# pqm_v2_page2.net
KiCad netlist of a schematic drawn in Altium Designer
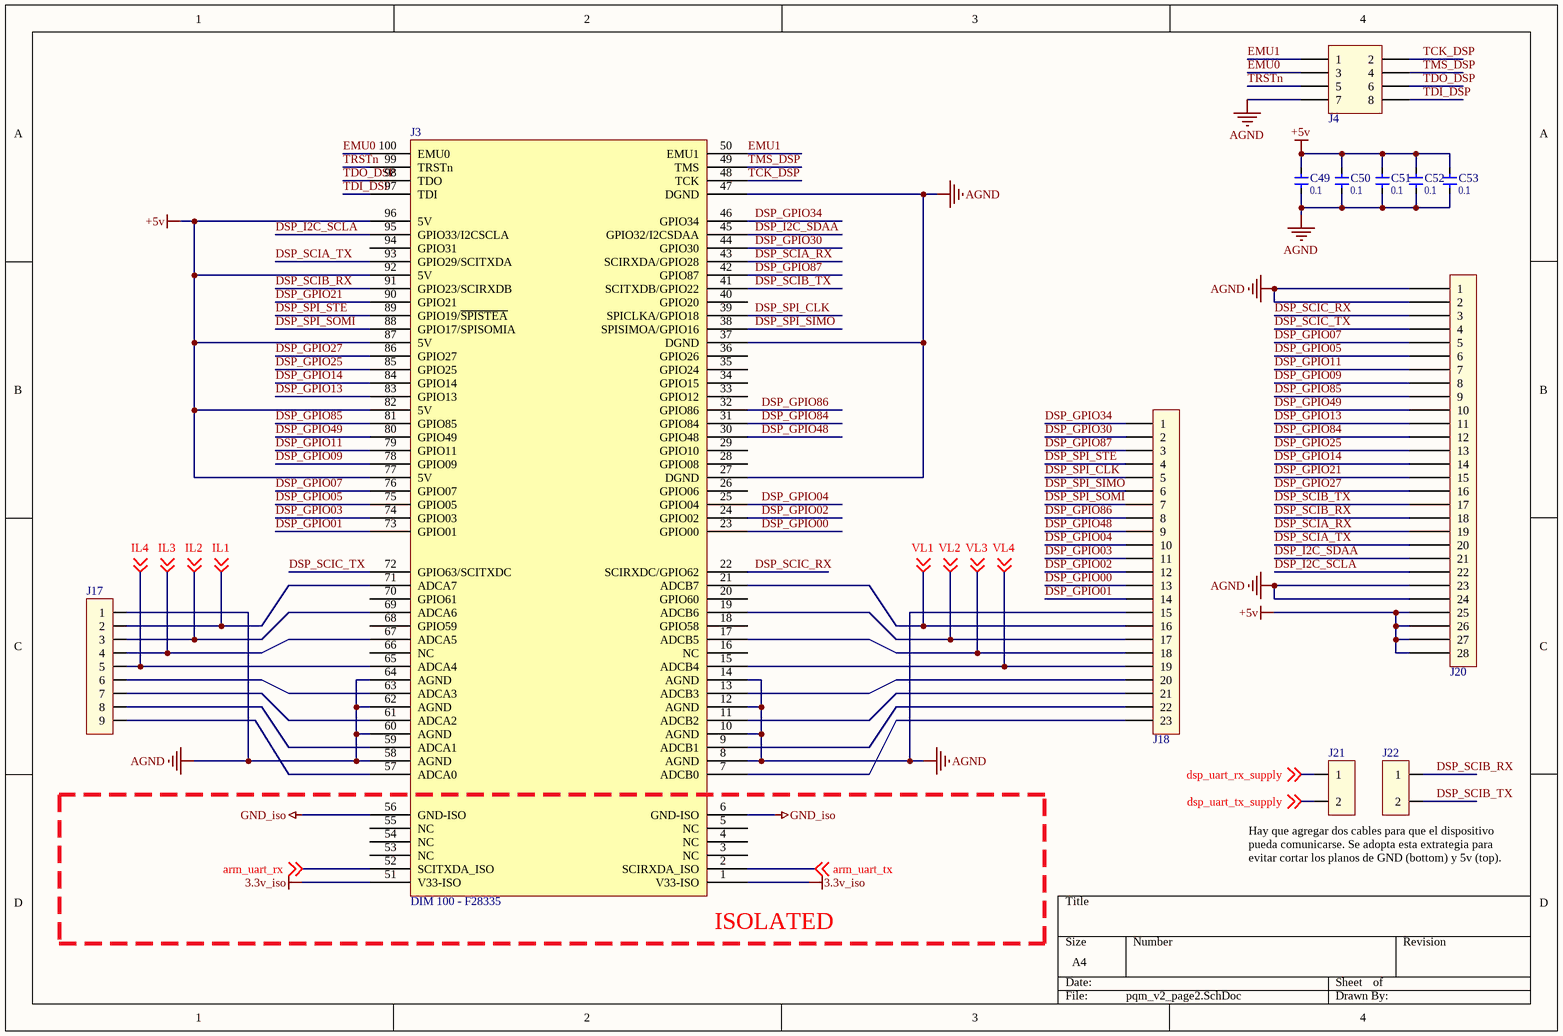
[diagram p0: pqm_v2_page2.SchDoc]

(export (version "E")
  (design (tool "Eeschema 10.0.6"))
  (components
    (comp (ref "C49")
      (value "0.1")
      (footprint "CAPC2013X110N")
      (description "CAP CER 0.1UF 25V 10% X7R 0805")
      (fields (field (name "MANUFACTURER") "Yageo") (field (name "TOLERANCE") "10%"))
      (libsource (lib "pqm_v2_lib_cap") (part "CAP_CC0805KRX7R8BB104_YAGEO"))
    )
    (comp (ref "C50")
      (value "0.1")
      (footprint "CAPC2013X110N")
      (description "CAP CER 0.1UF 25V 10% X7R 0805")
      (fields (field (name "MANUFACTURER") "Yageo") (field (name "TOLERANCE") "10%"))
      (libsource (lib "pqm_v2_lib_cap") (part "CAP_CC0805KRX7R8BB104_YAGEO"))
    )
    (comp (ref "C51")
      (value "0.1")
      (footprint "CAPC2013X110N")
      (description "CAP CER 0.1UF 25V 10% X7R 0805")
      (fields (field (name "MANUFACTURER") "Yageo") (field (name "TOLERANCE") "10%"))
      (libsource (lib "pqm_v2_lib_cap") (part "CAP_CC0805KRX7R8BB104_YAGEO"))
    )
    (comp (ref "C52")
      (value "0.1")
      (footprint "CAPC2013X110N")
      (description "CAP CER 0.1UF 25V 10% X7R 0805")
      (fields (field (name "MANUFACTURER") "Yageo") (field (name "TOLERANCE") "10%"))
      (libsource (lib "pqm_v2_lib_cap") (part "CAP_CC0805KRX7R8BB104_YAGEO"))
    )
    (comp (ref "C53")
      (value "0.1")
      (footprint "CAPC2013X110N")
      (description "CAP CER 0.1UF 25V 10% X7R 0805")
      (fields (field (name "MANUFACTURER") "Yageo") (field (name "TOLERANCE") "10%"))
      (libsource (lib "pqm_v2_lib_cap") (part "CAP_CC0805KRX7R8BB104_YAGEO"))
    )
    (comp (ref "J3")
      (value "DIM 100 - F28335")
      (footprint "DIMM1.27-2V100")
      (fields
        (field (name "DIGIKEY PART NUMBER") "A121375-ND")
        (field (name "MANUFACTURER PART NUMBER") "5390213-1")
        (field (name "MOUSER PART NUMBER") "571-5390213-1")
      )
      (libsource (lib "pqm_v2_lib_connectors") (part "CON_DIM_100"))
    )
    (comp (ref "J4")
      (value "CON_Header_2X4")
      (footprint "HDR2X4")
      (libsource (lib "pqm_v2_lib_connectors") (part "CON_Header_2X4"))
    )
    (comp (ref "J17")
      (value "COM_HeaderX9")
      (footprint "HDRX9")
      (libsource (lib "pqm_v2_lib_connectors") (part "COM_HeaderX9"))
    )
    (comp (ref "J18")
      (value "Header_DSP_1")
      (footprint "HEADER_DSP_1")
      (libsource (lib "pqm_v2_lib_connectors") (part "Header_DSP_1"))
    )
    (comp (ref "J20")
      (value "CON_HeaderX30")
      (footprint "HeaderX30")
      (libsource (lib "pqm_v2_lib_connectors") (part "CON_HeaderX30"))
    )
    (comp (ref "J21") (value "CON_RADX2b") (footprint "RAD2b") (libsource (lib "") (part "CON_RADX2b_1")))
    (comp (ref "J22")
      (value "CON_RADX2b")
      (footprint "RAD2b")
      (libsource (lib "pqm_v2_lib_connectors") (part "CON_RADX2b"))
    )
  )
  (nets
    (net (code "1") (name "+5v") (class "Default")
      (node (ref "C49") (pin "1") (pinfunction "T1_1") (pintype "passive"))
      (node (ref "C50") (pin "1") (pinfunction "T1_1") (pintype "passive"))
      (node (ref "C51") (pin "1") (pinfunction "T1_1") (pintype "passive"))
      (node (ref "C52") (pin "1") (pinfunction "T1_1") (pintype "passive"))
      (node (ref "C53") (pin "1") (pinfunction "T1_1") (pintype "passive"))
      (node (ref "J20") (pin "25") (pinfunction "25_25") (pintype "passive"))
      (node (ref "J20") (pin "26") (pinfunction "26_26") (pintype "passive"))
      (node (ref "J20") (pin "27") (pinfunction "27_27") (pintype "passive"))
      (node (ref "J20") (pin "28") (pinfunction "28_28") (pintype "passive"))
      (node (ref "J3") (pin "77") (pinfunction "5V_77") (pintype "passive"))
      (node (ref "J3") (pin "82") (pinfunction "5V_82") (pintype "passive"))
      (node (ref "J3") (pin "87") (pinfunction "5V_87") (pintype "passive"))
      (node (ref "J3") (pin "92") (pinfunction "5V_92") (pintype "passive"))
      (node (ref "J3") (pin "96") (pinfunction "5V_96") (pintype "passive"))
    )
    (net (code "2") (name "/DSP_GPIO00") (class "Default")
      (node (ref "J18") (pin "13") (pinfunction "13_13") (pintype "passive"))
      (node (ref "J3") (pin "23") (pinfunction "GPIO00_23") (pintype "passive"))
    )
    (net (code "3") (name "/DSP_GPIO01") (class "Default")
      (node (ref "J18") (pin "14") (pinfunction "14_14") (pintype "passive"))
      (node (ref "J3") (pin "73") (pinfunction "GPIO01_73") (pintype "passive"))
    )
    (net (code "4") (name "/DSP_GPIO02") (class "Default")
      (node (ref "J18") (pin "12") (pinfunction "12_12") (pintype "passive"))
      (node (ref "J3") (pin "24") (pinfunction "GPIO02_24") (pintype "passive"))
    )
    (net (code "5") (name "/DSP_GPIO03") (class "Default")
      (node (ref "J18") (pin "11") (pinfunction "11_11") (pintype "passive"))
      (node (ref "J3") (pin "74") (pinfunction "GPIO03_74") (pintype "passive"))
    )
    (net (code "6") (name "/DSP_GPIO04") (class "Default")
      (node (ref "J18") (pin "10") (pinfunction "10_10") (pintype "passive"))
      (node (ref "J3") (pin "25") (pinfunction "GPIO04_25") (pintype "passive"))
    )
    (net (code "7") (name "/DSP_GPIO05") (class "Default")
      (node (ref "J20") (pin "6") (pinfunction "6_6") (pintype "passive"))
      (node (ref "J3") (pin "75") (pinfunction "GPIO05_75") (pintype "passive"))
    )
    (net (code "8") (name "/DSP_GPIO07") (class "Default")
      (node (ref "J20") (pin "5") (pinfunction "5_5") (pintype "passive"))
      (node (ref "J3") (pin "76") (pinfunction "GPIO07_76") (pintype "passive"))
    )
    (net (code "9") (name "/DSP_GPIO09") (class "Default")
      (node (ref "J20") (pin "8") (pinfunction "8_8") (pintype "passive"))
      (node (ref "J3") (pin "78") (pinfunction "GPIO09_78") (pintype "passive"))
    )
    (net (code "10") (name "/DSP_GPIO11") (class "Default")
      (node (ref "J20") (pin "7") (pinfunction "7_7") (pintype "passive"))
      (node (ref "J3") (pin "79") (pinfunction "GPIO11_79") (pintype "passive"))
    )
    (net (code "11") (name "/DSP_GPIO13") (class "Default")
      (node (ref "J20") (pin "11") (pinfunction "11_11") (pintype "passive"))
      (node (ref "J3") (pin "83") (pinfunction "GPIO13_83") (pintype "passive"))
    )
    (net (code "12") (name "/DSP_GPIO14") (class "Default")
      (node (ref "J20") (pin "14") (pinfunction "14_14") (pintype "passive"))
      (node (ref "J3") (pin "84") (pinfunction "GPIO14_84") (pintype "passive"))
    )
    (net (code "13") (name "/DSP_GPIO21") (class "Default")
      (node (ref "J20") (pin "15") (pinfunction "15_15") (pintype "passive"))
      (node (ref "J3") (pin "90") (pinfunction "GPIO21_90") (pintype "passive"))
    )
    (net (code "14") (name "/DSP_GPIO25") (class "Default")
      (node (ref "J20") (pin "13") (pinfunction "13_13") (pintype "passive"))
      (node (ref "J3") (pin "85") (pinfunction "GPIO25_85") (pintype "passive"))
    )
    (net (code "15") (name "/DSP_GPIO27") (class "Default")
      (node (ref "J20") (pin "16") (pinfunction "16_16") (pintype "passive"))
      (node (ref "J3") (pin "86") (pinfunction "GPIO27_86") (pintype "passive"))
    )
    (net (code "16") (name "/DSP_GPIO30") (class "Default")
      (node (ref "J18") (pin "2") (pinfunction "2_2") (pintype "passive"))
      (node (ref "J3") (pin "44") (pinfunction "GPIO30_44") (pintype "passive"))
    )
    (net (code "17") (name "/DSP_GPIO34") (class "Default")
      (node (ref "J18") (pin "1") (pinfunction "1_1") (pintype "passive"))
      (node (ref "J3") (pin "46") (pinfunction "GPIO34_46") (pintype "passive"))
    )
    (net (code "18") (name "/DSP_GPIO48") (class "Default")
      (node (ref "J18") (pin "9") (pinfunction "9_9") (pintype "passive"))
      (node (ref "J3") (pin "30") (pinfunction "GPIO48_30") (pintype "passive"))
    )
    (net (code "19") (name "/DSP_GPIO49") (class "Default")
      (node (ref "J20") (pin "10") (pinfunction "10_10") (pintype "passive"))
      (node (ref "J3") (pin "80") (pinfunction "GPIO49_80") (pintype "passive"))
    )
    (net (code "20") (name "/DSP_GPIO84") (class "Default")
      (node (ref "J20") (pin "12") (pinfunction "12_12") (pintype "passive"))
      (node (ref "J3") (pin "31") (pinfunction "GPIO84_31") (pintype "passive"))
    )
    (net (code "21") (name "/DSP_GPIO85") (class "Default")
      (node (ref "J20") (pin "9") (pinfunction "9_9") (pintype "passive"))
      (node (ref "J3") (pin "81") (pinfunction "GPIO85_81") (pintype "passive"))
    )
    (net (code "22") (name "/DSP_GPIO86") (class "Default")
      (node (ref "J18") (pin "8") (pinfunction "8_8") (pintype "passive"))
      (node (ref "J3") (pin "32") (pinfunction "GPIO86_32") (pintype "passive"))
    )
    (net (code "23") (name "/DSP_GPIO87") (class "Default")
      (node (ref "J18") (pin "3") (pinfunction "3_3") (pintype "passive"))
      (node (ref "J3") (pin "42") (pinfunction "GPIO87_42") (pintype "passive"))
    )
    (net (code "24") (name "/DSP_I2C_SCLA") (class "Default")
      (node (ref "J20") (pin "22") (pinfunction "22_22") (pintype "passive"))
      (node (ref "J3") (pin "95") (pinfunction "GPIO33/I2CSCLA_95") (pintype "passive"))
    )
    (net (code "25") (name "/DSP_I2C_SDAA") (class "Default")
      (node (ref "J20") (pin "21") (pinfunction "21_21") (pintype "passive"))
      (node (ref "J3") (pin "45") (pinfunction "GPIO32/I2CSDAA_45") (pintype "passive"))
    )
    (net (code "26") (name "/DSP_SCIA_RX") (class "Default")
      (node (ref "J20") (pin "19") (pinfunction "19_19") (pintype "passive"))
      (node (ref "J3") (pin "43") (pinfunction "SCIRXDA/GPIO28_43") (pintype "passive"))
    )
    (net (code "27") (name "/DSP_SCIA_TX") (class "Default")
      (node (ref "J20") (pin "20") (pinfunction "20_20") (pintype "passive"))
      (node (ref "J3") (pin "93") (pinfunction "GPIO29/SCITXDA_93") (pintype "passive"))
    )
    (net (code "28") (name "/DSP_SCIB_RX") (class "Default")
      (node (ref "J20") (pin "18") (pinfunction "18_18") (pintype "passive"))
      (node (ref "J22") (pin "1") (pinfunction "1_1") (pintype "passive"))
      (node (ref "J3") (pin "91") (pinfunction "GPIO23/SCIRXDB_91") (pintype "passive"))
    )
    (net (code "29") (name "/DSP_SCIB_TX") (class "Default")
      (node (ref "J20") (pin "17") (pinfunction "17_17") (pintype "passive"))
      (node (ref "J22") (pin "2") (pinfunction "2_2") (pintype "passive"))
      (node (ref "J3") (pin "41") (pinfunction "SCITXDB/GPIO22_41") (pintype "passive"))
    )
    (net (code "30") (name "/DSP_SCIC_RX") (class "Default")
      (node (ref "J20") (pin "3") (pinfunction "3_3") (pintype "passive"))
      (node (ref "J3") (pin "22") (pinfunction "SCIRXDC/GPIO62_22") (pintype "passive"))
    )
    (net (code "31") (name "/DSP_SCIC_TX") (class "Default")
      (node (ref "J20") (pin "4") (pinfunction "4_4") (pintype "passive"))
      (node (ref "J3") (pin "72") (pinfunction "GPIO63/SCITXDC_72") (pintype "passive"))
    )
    (net (code "32") (name "/DSP_SPI_CLK") (class "Default")
      (node (ref "J18") (pin "5") (pinfunction "5_5") (pintype "passive"))
      (node (ref "J3") (pin "39") (pinfunction "SPICLKA/GPIO18_39") (pintype "passive"))
    )
    (net (code "33") (name "/DSP_SPI_SIMO") (class "Default")
      (node (ref "J18") (pin "6") (pinfunction "6_6") (pintype "passive"))
      (node (ref "J3") (pin "38") (pinfunction "SPISIMOA/GPIO16_38") (pintype "passive"))
    )
    (net (code "34") (name "/DSP_SPI_SOMI") (class "Default")
      (node (ref "J18") (pin "7") (pinfunction "7_7") (pintype "passive"))
      (node (ref "J3") (pin "88") (pinfunction "GPIO17/SPISOMIA_88") (pintype "passive"))
    )
    (net (code "35") (name "/DSP_SPI_STE") (class "Default")
      (node (ref "J18") (pin "4") (pinfunction "4_4") (pintype "passive"))
      (node (ref "J3") (pin "89") (pinfunction "GPIO19/~{SPISTEA}_89") (pintype "passive"))
    )
    (net (code "36") (name "/EMU0") (class "Default")
      (node (ref "J3") (pin "100") (pinfunction "EMU0_100") (pintype "passive"))
      (node (ref "J4") (pin "3") (pinfunction "3_3") (pintype "passive"))
    )
    (net (code "37") (name "/EMU1") (class "Default")
      (node (ref "J3") (pin "50") (pinfunction "EMU1_50") (pintype "passive"))
      (node (ref "J4") (pin "1") (pinfunction "1_1") (pintype "passive"))
    )
    (net (code "38") (name "/TCK_DSP") (class "Default")
      (node (ref "J3") (pin "48") (pinfunction "TCK_48") (pintype "passive"))
      (node (ref "J4") (pin "2") (pinfunction "2_2") (pintype "passive"))
    )
    (net (code "39") (name "/TDI_DSP") (class "Default")
      (node (ref "J3") (pin "97") (pinfunction "TDI_97") (pintype "passive"))
      (node (ref "J4") (pin "8") (pinfunction "8_8") (pintype "passive"))
    )
    (net (code "40") (name "/TDO_DSP") (class "Default")
      (node (ref "J3") (pin "98") (pinfunction "TDO_98") (pintype "passive"))
      (node (ref "J4") (pin "6") (pinfunction "6_6") (pintype "passive"))
    )
    (net (code "41") (name "/TMS_DSP") (class "Default")
      (node (ref "J3") (pin "49") (pinfunction "TMS_49") (pintype "passive"))
      (node (ref "J4") (pin "4") (pinfunction "4_4") (pintype "passive"))
    )
    (net (code "42") (name "/TRSTn") (class "Default")
      (node (ref "J3") (pin "99") (pinfunction "TRSTn_99") (pintype "passive"))
      (node (ref "J4") (pin "5") (pinfunction "5_5") (pintype "passive"))
    )
    (net (code "43") (name "3.3v_iso") (class "Default")
      (node (ref "J3") (pin "1") (pinfunction "V33-ISO_1") (pintype "passive"))
      (node (ref "J3") (pin "51") (pinfunction "V33-ISO_51") (pintype "passive"))
    )
    (net (code "44") (name "AGND") (class "Default")
      (node (ref "C49") (pin "2") (pinfunction "T2_2") (pintype "passive"))
      (node (ref "C50") (pin "2") (pinfunction "T2_2") (pintype "passive"))
      (node (ref "C51") (pin "2") (pinfunction "T2_2") (pintype "passive"))
      (node (ref "C52") (pin "2") (pinfunction "T2_2") (pintype "passive"))
      (node (ref "C53") (pin "2") (pinfunction "T2_2") (pintype "passive"))
      (node (ref "J17") (pin "1") (pinfunction "1_1") (pintype "passive"))
      (node (ref "J18") (pin "15") (pinfunction "15_15") (pintype "passive"))
      (node (ref "J20") (pin "1") (pinfunction "1_1") (pintype "passive"))
      (node (ref "J20") (pin "2") (pinfunction "2_2") (pintype "passive"))
      (node (ref "J20") (pin "23") (pinfunction "23_23") (pintype "passive"))
      (node (ref "J20") (pin "24") (pinfunction "24_24") (pintype "passive"))
      (node (ref "J3") (pin "10") (pinfunction "AGND_10") (pintype "passive"))
      (node (ref "J3") (pin "12") (pinfunction "AGND_12") (pintype "passive"))
      (node (ref "J3") (pin "14") (pinfunction "AGND_14") (pintype "passive"))
      (node (ref "J3") (pin "27") (pinfunction "DGND_27") (pintype "passive"))
      (node (ref "J3") (pin "37") (pinfunction "DGND_37") (pintype "passive"))
      (node (ref "J3") (pin "47") (pinfunction "DGND_47") (pintype "passive"))
      (node (ref "J3") (pin "58") (pinfunction "AGND_58") (pintype "passive"))
      (node (ref "J3") (pin "60") (pinfunction "AGND_60") (pintype "passive"))
      (node (ref "J3") (pin "62") (pinfunction "AGND_62") (pintype "passive"))
      (node (ref "J3") (pin "64") (pinfunction "AGND_64") (pintype "passive"))
      (node (ref "J3") (pin "8") (pinfunction "AGND_8") (pintype "passive"))
      (node (ref "J4") (pin "7") (pinfunction "7_7") (pintype "passive"))
    )
    (net (code "45") (name "GND_iso") (class "Default")
      (node (ref "J3") (pin "56") (pinfunction "GND-ISO_56") (pintype "passive"))
      (node (ref "J3") (pin "6") (pinfunction "GND-ISO_6") (pintype "passive"))
    )
    (net (code "46") (name "IL1") (class "Default")
      (node (ref "J17") (pin "2") (pinfunction "2_2") (pintype "passive"))
      (node (ref "J3") (pin "71") (pinfunction "ADCA7_71") (pintype "passive"))
    )
    (net (code "47") (name "IL2") (class "Default")
      (node (ref "J17") (pin "3") (pinfunction "3_3") (pintype "passive"))
      (node (ref "J3") (pin "69") (pinfunction "ADCA6_69") (pintype "passive"))
    )
    (net (code "48") (name "IL3") (class "Default")
      (node (ref "J17") (pin "4") (pinfunction "4_4") (pintype "passive"))
      (node (ref "J3") (pin "67") (pinfunction "ADCA5_67") (pintype "passive"))
    )
    (net (code "49") (name "IL4") (class "Default")
      (node (ref "J17") (pin "5") (pinfunction "5_5") (pintype "passive"))
      (node (ref "J3") (pin "65") (pinfunction "ADCA4_65") (pintype "passive"))
    )
    (net (code "50") (name "Net-(J3-ADCA0)") (class "Default")
      (node (ref "J17") (pin "9") (pinfunction "9_9") (pintype "passive"))
      (node (ref "J3") (pin "57") (pinfunction "ADCA0_57") (pintype "passive"))
    )
    (net (code "51") (name "Net-(J3-ADCA1)") (class "Default")
      (node (ref "J17") (pin "8") (pinfunction "8_8") (pintype "passive"))
      (node (ref "J3") (pin "59") (pinfunction "ADCA1_59") (pintype "passive"))
    )
    (net (code "52") (name "Net-(J3-ADCA2)") (class "Default")
      (node (ref "J17") (pin "7") (pinfunction "7_7") (pintype "passive"))
      (node (ref "J3") (pin "61") (pinfunction "ADCA2_61") (pintype "passive"))
    )
    (net (code "53") (name "Net-(J3-ADCA3)") (class "Default")
      (node (ref "J17") (pin "6") (pinfunction "6_6") (pintype "passive"))
      (node (ref "J3") (pin "63") (pinfunction "ADCA3_63") (pintype "passive"))
    )
    (net (code "54") (name "Net-(J3-ADCB0)") (class "Default")
      (node (ref "J18") (pin "23") (pinfunction "23_23") (pintype "passive"))
      (node (ref "J3") (pin "7") (pinfunction "ADCB0_7") (pintype "passive"))
    )
    (net (code "55") (name "Net-(J3-ADCB1)") (class "Default")
      (node (ref "J18") (pin "22") (pinfunction "22_22") (pintype "passive"))
      (node (ref "J3") (pin "9") (pinfunction "ADCB1_9") (pintype "passive"))
    )
    (net (code "56") (name "Net-(J3-ADCB2)") (class "Default")
      (node (ref "J18") (pin "21") (pinfunction "21_21") (pintype "passive"))
      (node (ref "J3") (pin "11") (pinfunction "ADCB2_11") (pintype "passive"))
    )
    (net (code "57") (name "Net-(J3-ADCB3)") (class "Default")
      (node (ref "J18") (pin "20") (pinfunction "20_20") (pintype "passive"))
      (node (ref "J3") (pin "13") (pinfunction "ADCB3_13") (pintype "passive"))
    )
    (net (code "58") (name "VL1") (class "Default")
      (node (ref "J18") (pin "16") (pinfunction "16_16") (pintype "passive"))
      (node (ref "J3") (pin "21") (pinfunction "ADCB7_21") (pintype "passive"))
    )
    (net (code "59") (name "VL2") (class "Default")
      (node (ref "J18") (pin "17") (pinfunction "17_17") (pintype "passive"))
      (node (ref "J3") (pin "19") (pinfunction "ADCB6_19") (pintype "passive"))
    )
    (net (code "60") (name "VL3") (class "Default")
      (node (ref "J18") (pin "18") (pinfunction "18_18") (pintype "passive"))
      (node (ref "J3") (pin "17") (pinfunction "ADCB5_17") (pintype "passive"))
    )
    (net (code "61") (name "VL4") (class "Default")
      (node (ref "J18") (pin "19") (pinfunction "19_19") (pintype "passive"))
      (node (ref "J3") (pin "15") (pinfunction "ADCB4_15") (pintype "passive"))
    )
    (net (code "62") (name "arm_uart_rx") (class "Default")
      (node (ref "J3") (pin "52") (pinfunction "SCITXDA_ISO_52") (pintype "passive"))
    )
    (net (code "63") (name "arm_uart_tx") (class "Default")
      (node (ref "J3") (pin "2") (pinfunction "SCIRXDA_ISO_2") (pintype "passive"))
    )
    (net (code "64") (name "dsp_uart_rx_supply") (class "Default")
      (node (ref "J21") (pin "1") (pinfunction "1_1") (pintype "passive"))
    )
    (net (code "65") (name "dsp_uart_tx_supply") (class "Default")
      (node (ref "J21") (pin "2") (pinfunction "2_2") (pintype "passive"))
    )
    (net (code "66") (name "unconnected-(J3-GPIO06-Pad26)") (class "Default")
      (node (ref "J3") (pin "26") (pinfunction "GPIO06_26") (pintype "passive"))
    )
    (net (code "67") (name "unconnected-(J3-GPIO08-Pad28)") (class "Default")
      (node (ref "J3") (pin "28") (pinfunction "GPIO08_28") (pintype "passive"))
    )
    (net (code "68") (name "unconnected-(J3-GPIO10-Pad29)") (class "Default")
      (node (ref "J3") (pin "29") (pinfunction "GPIO10_29") (pintype "passive"))
    )
    (net (code "69") (name "unconnected-(J3-GPIO12-Pad33)") (class "Default")
      (node (ref "J3") (pin "33") (pinfunction "GPIO12_33") (pintype "passive"))
    )
    (net (code "70") (name "unconnected-(J3-GPIO15-Pad34)") (class "Default")
      (node (ref "J3") (pin "34") (pinfunction "GPIO15_34") (pintype "passive"))
    )
    (net (code "71") (name "unconnected-(J3-GPIO20-Pad40)") (class "Default")
      (node (ref "J3") (pin "40") (pinfunction "GPIO20_40") (pintype "passive"))
    )
    (net (code "72") (name "unconnected-(J3-GPIO24-Pad35)") (class "Default")
      (node (ref "J3") (pin "35") (pinfunction "GPIO24_35") (pintype "passive"))
    )
    (net (code "73") (name "unconnected-(J3-GPIO26-Pad36)") (class "Default")
      (node (ref "J3") (pin "36") (pinfunction "GPIO26_36") (pintype "passive"))
    )
    (net (code "74") (name "unconnected-(J3-GPIO31-Pad94)") (class "Default")
      (node (ref "J3") (pin "94") (pinfunction "GPIO31_94") (pintype "passive"))
    )
    (net (code "75") (name "unconnected-(J3-GPIO58-Pad18)") (class "Default")
      (node (ref "J3") (pin "18") (pinfunction "GPIO58_18") (pintype "passive"))
    )
    (net (code "76") (name "unconnected-(J3-GPIO59-Pad68)") (class "Default")
      (node (ref "J3") (pin "68") (pinfunction "GPIO59_68") (pintype "passive"))
    )
    (net (code "77") (name "unconnected-(J3-GPIO60-Pad20)") (class "Default")
      (node (ref "J3") (pin "20") (pinfunction "GPIO60_20") (pintype "passive"))
    )
    (net (code "78") (name "unconnected-(J3-GPIO61-Pad70)") (class "Default")
      (node (ref "J3") (pin "70") (pinfunction "GPIO61_70") (pintype "passive"))
    )
    (net (code "79") (name "unconnected-(J3-NC-Pad3)") (class "Default")
      (node (ref "J3") (pin "3") (pinfunction "NC_3") (pintype "passive"))
    )
    (net (code "80") (name "unconnected-(J3-NC-Pad4)") (class "Default")
      (node (ref "J3") (pin "4") (pinfunction "NC_4") (pintype "passive"))
    )
    (net (code "81") (name "unconnected-(J3-NC-Pad5)") (class "Default")
      (node (ref "J3") (pin "5") (pinfunction "NC_5") (pintype "passive"))
    )
    (net (code "82") (name "unconnected-(J3-NC-Pad16)") (class "Default")
      (node (ref "J3") (pin "16") (pinfunction "NC_16") (pintype "passive"))
    )
    (net (code "83") (name "unconnected-(J3-NC-Pad53)") (class "Default")
      (node (ref "J3") (pin "53") (pinfunction "NC_53") (pintype "passive"))
    )
    (net (code "84") (name "unconnected-(J3-NC-Pad54)") (class "Default")
      (node (ref "J3") (pin "54") (pinfunction "NC_54") (pintype "passive"))
    )
    (net (code "85") (name "unconnected-(J3-NC-Pad55)") (class "Default")
      (node (ref "J3") (pin "55") (pinfunction "NC_55") (pintype "passive"))
    )
    (net (code "86") (name "unconnected-(J3-NC-Pad66)") (class "Default")
      (node (ref "J3") (pin "66") (pinfunction "NC_66") (pintype "passive"))
    )
  )
)
